# NGUON.net
KiCad netlist of a schematic drawn in Altium Designer
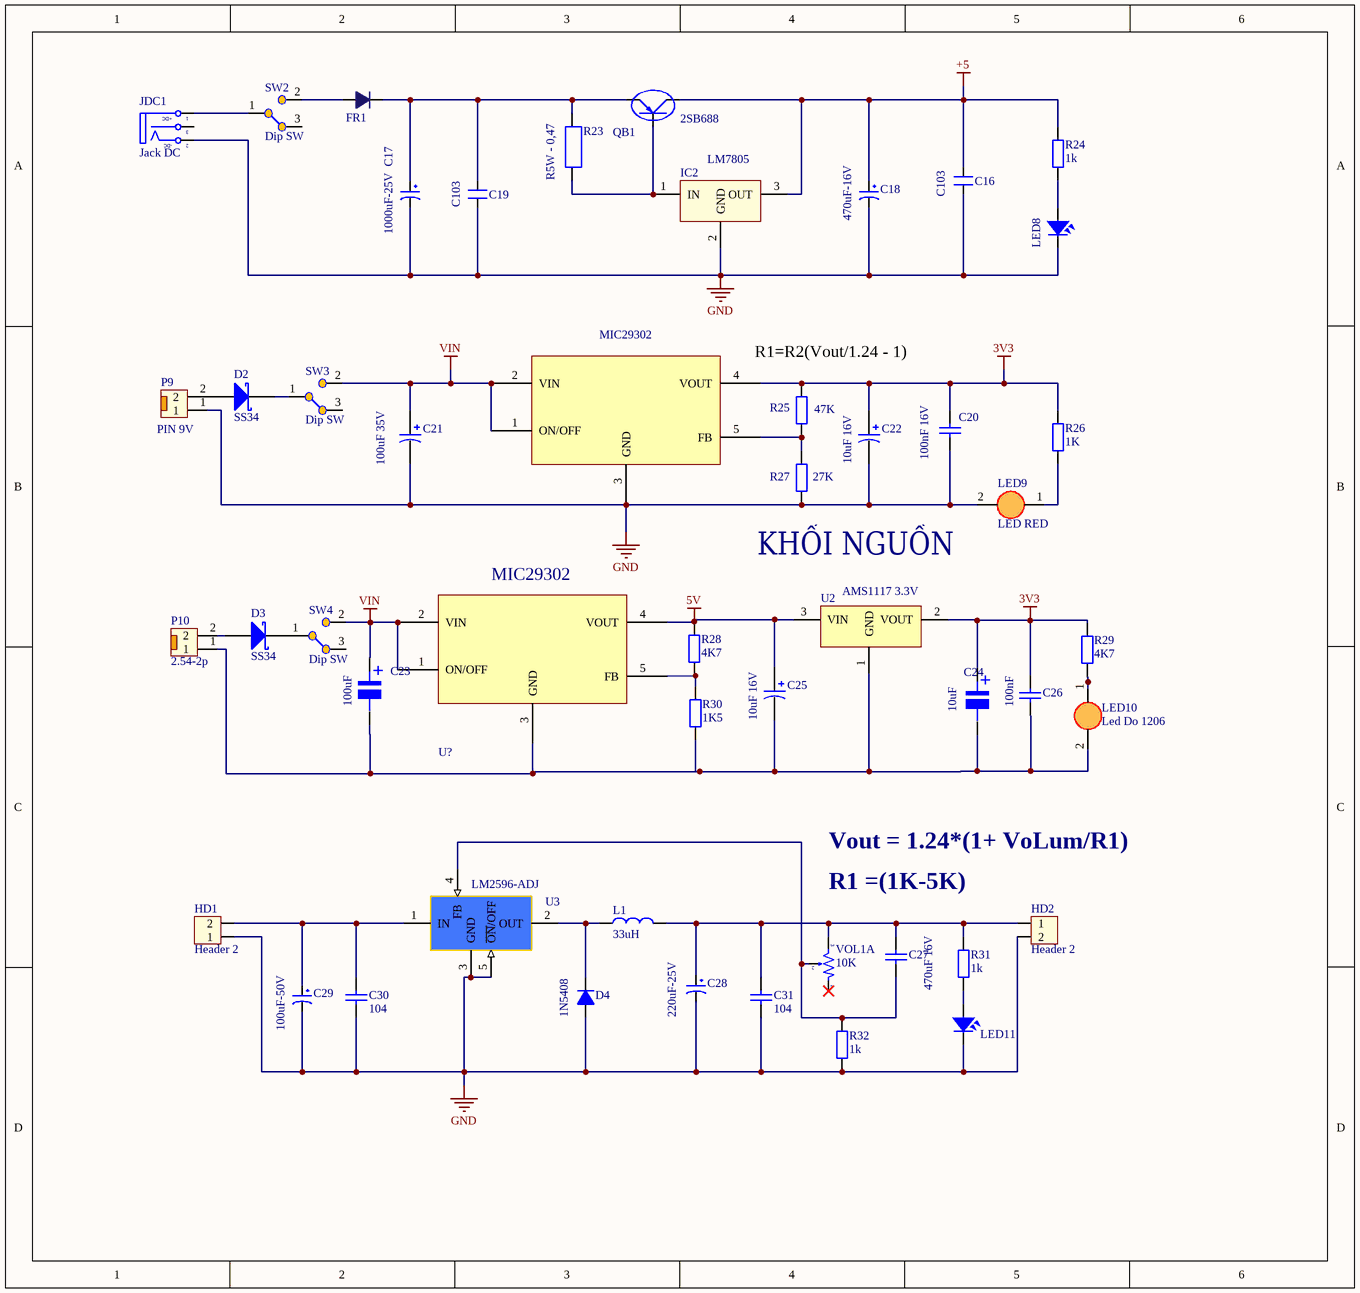
[diagram p0: NGUON.SchDoc]

(export (version "E")
  (design (tool "Eeschema 10.0.6"))
  (components
    (comp (ref "C16")
      (value "C103")
      (footprint "CN1")
      (description "Cap np  1pF - 472pF")
      (libsource (lib "syhaunguyen") (part "CN1"))
    )
    (comp (ref "C17")
      (value "1000uF-25V")
      (footprint "tu hoa 13mm")
      (description "Cắm")
      (libsource (lib "NhomLib") (part "Tu Hoa 1000uF 25V 13x21"))
    )
    (comp (ref "C18")
      (value "470uF-16V")
      (footprint "tu hoa 8mm")
      (description "Cắm")
      (libsource (lib "NhomLib") (part "Tu Hoa 470uF 16V 8x11"))
    )
    (comp (ref "C19")
      (value "C103")
      (footprint "CN1")
      (description "Cap np  1pF - 472pF")
      (libsource (lib "syhaunguyen") (part "CN1"))
    )
    (comp (ref "C20")
      (value "100nF 16V")
      (footprint "tu 0805")
      (description "Dán")
      (libsource (lib "SCH Chuan") (part "Tu 0805 22pF 50V 10%"))
    )
    (comp (ref "C21")
      (value "100uF 35V")
      (footprint "CAP_ALUM_SMD_100102_TYPE_G")
      (description "CAP ALUM 330uF 20% 35V SMD")
      (fields (field (name "MPN") "EEE-FK1C331P") (field (name "MFR") "Panasonic"))
      (libsource (lib "NhomLib") (part "EEE-FK1C331P"))
    )
    (comp (ref "C22")
      (value "10uF 16V")
      (footprint "CAP_ALUM_SMD_5054_TYPE_C")
      (description "CAP ALUM 33uF 20% 16V SMD")
      (fields (field (name "MPN") "EEE-FK1C330P") (field (name "MFR") "Panasonic"))
      (libsource (lib "NhomLib") (part "EEE-FK1C330P"))
    )
    (comp (ref "C23")
      (value "100uF")
      (footprint "tu nhom 10 (g)")
      (description "Dán")
      (libsource (lib "NhomLib") (part "Tu Nhom 100uF 35V"))
    )
    (comp (ref "C24")
      (value "10uF")
      (footprint "tu nhom 4 (b)")
      (description "Dán")
      (libsource (lib "NhomLib") (part "Tu Nhom 10uF 16V"))
    )
    (comp (ref "C25")
      (value "10uF 16V")
      (footprint "CAP_ALUM_SMD_5054_TYPE_C")
      (description "CAP ALUM 33uF 20% 16V SMD")
      (fields (field (name "MPN") "EEE-FK1C330P") (field (name "MFR") "Panasonic"))
      (libsource (lib "NhomLib") (part "EEE-FK1C330P"))
    )
    (comp (ref "C26")
      (value "100nF")
      (footprint "tu 0805")
      (description "Dán")
      (libsource (lib "NhomLib") (part "Tu 0805 220nF 50V 10%"))
    )
    (comp (ref "C27")
      (value "470uF 16V")
      (footprint "tu gom")
      (description "Cắm")
      (libsource (lib "NhomLib") (part "Tu gom 100 50V"))
    )
    (comp (ref "C28")
      (value "220uF-25V")
      (footprint "Tu hoa 8mm")
      (description "Cắm")
      (libsource (lib "NhomLib") (part "Tu Hoa 220uF 25V 8x10"))
    )
    (comp (ref "C29")
      (value "100uF-50V")
      (footprint "tu hoa 8mm")
      (description "Cắm")
      (libsource (lib "NhomLib") (part "Tu Hoa 100uF 50V 8x11"))
    )
    (comp (ref "C30")
      (value "104")
      (footprint "tu gom")
      (description "Cắm")
      (libsource (lib "NhomLib") (part "Tu gom 100 50V"))
    )
    (comp (ref "C31")
      (value "104")
      (footprint "tu gom")
      (description "Cắm")
      (libsource (lib "NhomLib") (part "Tu gom 100 50V"))
    )
    (comp (ref "D2")
      (value "SS34")
      (footprint "DIODE_DO214AC_SMA")
      (description "DIODE SCHOTTKY 40V 3A SMA")
      (libsource (lib "NhomLib") (part "SS34"))
    )
    (comp (ref "D3")
      (value "SS34")
      (footprint "DIODE_DO214AC_SMA")
      (description "DIODE SCHOTTKY 40V 3A SMA")
      (libsource (lib "NhomLib") (part "SS34"))
    )
    (comp (ref "D4")
      (value "1N5408")
      (footprint "D5A")
      (description "Diode 5A")
      (libsource (lib "syhaunguyen") (part "D5A"))
    )
    (comp (ref "FR1")
      (value "Diode FR307")
      (footprint "FR307")
      (description "Diode RECT FAST REC 1000V 3A DO-201AD")
      (fields (field (name "PUBLISHER") "Altium Limited"))
      (libsource (lib "VPMyLibrary") (part "Diode FR307"))
    )
    (comp (ref "HD1")
      (value "Header 2")
      (footprint "HED2")
      (description "Header 2 (Green)")
      (libsource (lib "") (part "Hed2_1"))
    )
    (comp (ref "HD2")
      (value "Header 2")
      (footprint "HED2")
      (description "Header 2 (Green)")
      (libsource (lib "NhomLib") (part "Hed2"))
    )
    (comp (ref "IC2")
      (value "LM7805")
      (footprint "QTO-220H3")
      (description "On ap +, from + 5 to + 24VDC")
      (libsource (lib "NhomLib") (part "LM78xx"))
    )
    (comp (ref "JDC1")
      (value "Jack DC")
      (footprint "DC-IN")
      (description "Cắm")
      (libsource (lib "NhomLib") (part "Jack DC"))
    )
    (comp (ref "L1")
      (value "33uH")
      (footprint "R1/4W")
      (description "Cắm")
      (libsource (lib "NhomLib") (part "Cuon cam 220uH"))
    )
    (comp (ref "LED8")
      (value "LED")
      (footprint "LED-5-RED")
      (description "LED Single colour Green and Red")
      (libsource (lib "syhaunguyen") (part "LED"))
    )
    (comp (ref "LED9")
      (value "LED RED")
      (footprint "led 0805")
      (description "Dán")
      (libsource (lib "SCH Chuan") (part "Led 0805 Do"))
    )
    (comp (ref "LED10")
      (value "Led Do 1206")
      (footprint "led 1206")
      (description "Dán")
      (libsource (lib "NhomLib") (part "Led 1206 Do"))
    )
    (comp (ref "LED11")
      (value "LED")
      (footprint "LED-5-RED")
      (description "LED Single colour Green and Red")
      (libsource (lib "syhaunguyen") (part "LED"))
    )
    (comp (ref "MIC2")
      (value "MIC29302")
      (footprint "Mic5V")
      (description "3A")
      (libsource (lib "node_mcu") (part "Mic5V"))
    )
    (comp (ref "MIC3")
      (value "U?")
      (footprint "Mic5V")
      (description "3A")
      (libsource (lib "node_mcu") (part "Mic5V"))
    )
    (comp (ref "P9")
      (value "PIN 9V")
      (footprint "Header Duc Thang 2P 2.54")
      (description "Cắm")
      (libsource (lib "NhomLib") (part "Header 2.54-2p Duc Thang"))
    )
    (comp (ref "P10")
      (value "2.54-2p")
      (footprint "Header Duc Thang 2P 2.54")
      (description "Cắm")
      (libsource (lib "NhomLib") (part "Header 2.54-2p Duc Thang"))
    )
    (comp (ref "QB1")
      (value "2SB688")
      (footprint "QTO-247")
      (description "Cắm")
      (libsource (lib "NhomLib") (part "B688"))
    )
    (comp (ref "R23")
      (value "R5W - 0,47")
      (footprint "R5W")
      (description "Resistor 5W")
      (libsource (lib "syhaunguyen") (part "R5W"))
    )
    (comp (ref "R24")
      (value "1k")
      (footprint "R1/4W")
      (description "Resistor 1/4W")
      (libsource (lib "syhaunguyen") (part "R1/4W"))
    )
    (comp (ref "R25")
      (value "47K")
      (footprint "tro 0805")
      (description "Dán")
      (libsource (lib "NhomLib") (part "Tro 0805 5% 10k"))
    )
    (comp (ref "R26")
      (value "1K")
      (footprint "tro 0805")
      (description "Dán")
      (libsource (lib "NhomLib") (part "Tro 0805 5% 10k"))
    )
    (comp (ref "R27")
      (value "27K")
      (footprint "tro 0805")
      (description "Dán")
      (libsource (lib "NhomLib") (part "Tro 0805 5% 10k"))
    )
    (comp (ref "R28")
      (value "4K7")
      (footprint "tro 0805")
      (description "Dán")
      (libsource (lib "SCH Chuan") (part "Tro 0805 5% 10k"))
    )
    (comp (ref "R29")
      (value "4K7")
      (footprint "tro 0805")
      (description "Dán")
      (libsource (lib "SCH Chuan") (part "Tro 0805 5% 10k"))
    )
    (comp (ref "R30")
      (value "1K5")
      (footprint "tro 0805")
      (description "Dán")
      (libsource (lib "SCH Chuan") (part "Tro 0805 5% 10k"))
    )
    (comp (ref "R31")
      (value "1k")
      (footprint "R1/4W")
      (description "Resistor 1/4W")
      (libsource (lib "syhaunguyen") (part "R1/4W"))
    )
    (comp (ref "R32")
      (value "1k")
      (footprint "R1/4W")
      (description "Resistor 1/4W")
      (libsource (lib "syhaunguyen") (part "R1/4W"))
    )
    (comp (ref "SW2")
      (value "Dip SW")
      (footprint "SW3P")
      (description "Dip Switch 3 pin")
      (libsource (lib "VPMyLibrary") (part "Switch3P"))
    )
    (comp (ref "SW3")
      (value "Dip SW")
      (footprint "SW3P")
      (description "Dip Switch 3 pin")
      (libsource (lib "VPMyLibrary") (part "Switch3P"))
    )
    (comp (ref "SW4")
      (value "Dip SW")
      (footprint "SW3P")
      (description "Dip Switch 3 pin")
      (libsource (lib "VPMyLibrary") (part "Switch3P"))
    )
    (comp (ref "U2")
      (value "AMS1117 3.3V")
      (footprint "SOT223")
      (description "Dán")
      (libsource (lib "NhomLib") (part "AMS1117 3.3V"))
    )
    (comp (ref "U3")
      (value "LM2596-ADJ")
      (footprint "D2-PACK5")
      (description "Simple Switcher 3A Step Down Voltage Regulator")
      (fields (field (name "PUBLISHER") "Altium Limited"))
      (libsource (lib "VPMyLibrary") (part "LM2596"))
    )
    (comp (ref "VOL1")
      (value "10K")
      (footprint "VR1")
      (description "Volume control Dual")
      (libsource (lib "SCH Chuan") (part "VOL-D"))
    )
  )
  (nets
    (net (code "1") (name "+5") (class "Default")
      (node (ref "C16") (pin "2") (pinfunction "2_2") (pintype "passive"))
      (node (ref "C18") (pin "1") (pinfunction "1_1") (pintype "passive"))
      (node (ref "IC2") (pin "3") (pinfunction "OUT_3") (pintype "passive"))
      (node (ref "QB1") (pin "2") (pinfunction "C_2") (pintype "passive"))
      (node (ref "R24") (pin "2") (pinfunction "2_2") (pintype "passive"))
    )
    (net (code "2") (name "3V3") (class "Default")
      (node (ref "C20") (pin "1") (pinfunction "1_1") (pintype "passive"))
      (node (ref "C22") (pin "1") (pinfunction "1_1") (pintype "passive"))
      (node (ref "C24") (pin "1") (pinfunction "1_1") (pintype "passive"))
      (node (ref "C26") (pin "1") (pinfunction "1_1") (pintype "passive"))
      (node (ref "MIC2") (pin "4") (pinfunction "VOUT_4") (pintype "passive"))
      (node (ref "R25") (pin "1") (pinfunction "1_1") (pintype "passive"))
      (node (ref "R26") (pin "2") (pinfunction "2_2") (pintype "passive"))
      (node (ref "R29") (pin "1") (pinfunction "1_1") (pintype "passive"))
      (node (ref "U2") (pin "2") (pinfunction "VOUT_2") (pintype "passive"))
    )
    (net (code "3") (name "5V") (class "Default")
      (node (ref "C25") (pin "1") (pinfunction "1_1") (pintype "passive"))
      (node (ref "MIC3") (pin "4") (pinfunction "VOUT_4") (pintype "passive"))
      (node (ref "R28") (pin "2") (pinfunction "2_2") (pintype "passive"))
      (node (ref "U2") (pin "3") (pinfunction "VIN_3") (pintype "passive"))
    )
    (net (code "4") (name "GND") (class "Default")
      (node (ref "C16") (pin "1") (pinfunction "1_1") (pintype "passive"))
      (node (ref "C17") (pin "2") (pinfunction "2_2") (pintype "passive"))
      (node (ref "C18") (pin "2") (pinfunction "2_2") (pintype "passive"))
      (node (ref "C19") (pin "1") (pinfunction "1_1") (pintype "passive"))
      (node (ref "C20") (pin "2") (pinfunction "2_2") (pintype "passive"))
      (node (ref "C21") (pin "2") (pinfunction "2_2") (pintype "passive"))
      (node (ref "C22") (pin "2") (pinfunction "2_2") (pintype "passive"))
      (node (ref "C28") (pin "2") (pinfunction "2_2") (pintype "passive"))
      (node (ref "C29") (pin "2") (pinfunction "2_2") (pintype "passive"))
      (node (ref "C30") (pin "2") (pinfunction "2_2") (pintype "passive"))
      (node (ref "C31") (pin "2") (pinfunction "2_2") (pintype "passive"))
      (node (ref "D4") (pin "1") (pinfunction "A_1") (pintype "passive"))
      (node (ref "HD1") (pin "1") (pinfunction "1_1") (pintype "passive"))
      (node (ref "HD2") (pin "2") (pinfunction "2_2") (pintype "passive"))
      (node (ref "IC2") (pin "2") (pinfunction "GND_2") (pintype "passive"))
      (node (ref "JDC1") (pin "2") (pinfunction "TN_2") (pintype "passive"))
      (node (ref "LED11") (pin "2") (pinfunction "2_2") (pintype "passive"))
      (node (ref "LED8") (pin "2") (pinfunction "2_2") (pintype "passive"))
      (node (ref "LED9") (pin "2") (pinfunction "K_2") (pintype "passive"))
      (node (ref "MIC2") (pin "3") (pinfunction "GND_3") (pintype "passive"))
      (node (ref "P9") (pin "1") (pinfunction "1_1") (pintype "passive"))
      (node (ref "R27") (pin "2") (pinfunction "2_2") (pintype "passive"))
      (node (ref "R32") (pin "1") (pinfunction "1_1") (pintype "passive"))
      (node (ref "U3") (pin "3") (pinfunction "GND_3") (pintype "power_in"))
      (node (ref "U3") (pin "5") (pinfunction "~{ON}/OFF_5") (pintype "input"))
    )
    (net (code "5") (name "Net-(C27-Pad1)") (class "Default")
      (node (ref "C27") (pin "1") (pinfunction "1_1") (pintype "passive"))
      (node (ref "C28") (pin "1") (pinfunction "1_1") (pintype "passive"))
      (node (ref "C31") (pin "1") (pinfunction "1_1") (pintype "passive"))
      (node (ref "HD2") (pin "1") (pinfunction "1_1") (pintype "passive"))
      (node (ref "L1") (pin "2") (pinfunction "2_2") (pintype "passive"))
      (node (ref "R31") (pin "2") (pinfunction "2_2") (pintype "passive"))
      (node (ref "VOL1") (pin "3") (pinfunction "3_3") (pintype "passive"))
    )
    (net (code "6") (name "Net-(D2-A)") (class "Default")
      (node (ref "D2") (pin "1") (pinfunction "A_1") (pintype "passive"))
      (node (ref "P9") (pin "2") (pinfunction "2_2") (pintype "passive"))
    )
    (net (code "7") (name "Net-(D2-K)") (class "Default")
      (node (ref "D2") (pin "2") (pinfunction "K_2") (pintype "passive"))
      (node (ref "SW3") (pin "1") (pinfunction "COM_1") (pintype "passive"))
    )
    (net (code "8") (name "Net-(D3-A)") (class "Default")
      (node (ref "D3") (pin "1") (pinfunction "A_1") (pintype "passive"))
      (node (ref "P10") (pin "2") (pinfunction "2_2") (pintype "passive"))
    )
    (net (code "9") (name "Net-(D3-K)") (class "Default")
      (node (ref "D3") (pin "2") (pinfunction "K_2") (pintype "passive"))
      (node (ref "SW4") (pin "1") (pinfunction "COM_1") (pintype "passive"))
    )
    (net (code "10") (name "Net-(D4-K)") (class "Default")
      (node (ref "D4") (pin "2") (pinfunction "K_2") (pintype "passive"))
      (node (ref "L1") (pin "1") (pinfunction "1_1") (pintype "passive"))
      (node (ref "U3") (pin "2") (pinfunction "OUT_2") (pintype "power_in"))
    )
    (net (code "11") (name "Net-(FR1-A)") (class "Default")
      (node (ref "FR1") (pin "1") (pinfunction "A_1") (pintype "passive"))
      (node (ref "SW2") (pin "2") (pinfunction "NC_2") (pintype "passive"))
    )
    (net (code "12") (name "Net-(FR1-K)") (class "Default")
      (node (ref "C17") (pin "1") (pinfunction "1_1") (pintype "passive"))
      (node (ref "C19") (pin "2") (pinfunction "2_2") (pintype "passive"))
      (node (ref "FR1") (pin "2") (pinfunction "K_2") (pintype "passive"))
      (node (ref "QB1") (pin "3") (pinfunction "E_3") (pintype "passive"))
      (node (ref "R23") (pin "2") (pinfunction "2_2") (pintype "passive"))
    )
    (net (code "13") (name "Net-(IC2-IN)") (class "Default")
      (node (ref "IC2") (pin "1") (pinfunction "IN_1") (pintype "passive"))
      (node (ref "QB1") (pin "1") (pinfunction "B_1") (pintype "passive"))
      (node (ref "R23") (pin "1") (pinfunction "1_1") (pintype "passive"))
    )
    (net (code "14") (name "Net-(JDC1-T)") (class "Default")
      (node (ref "JDC1") (pin "1") (pinfunction "T_1") (pintype "passive"))
      (node (ref "SW2") (pin "1") (pinfunction "COM_1") (pintype "passive"))
    )
    (net (code "15") (name "Net-(LED8-Pad1)") (class "Default")
      (node (ref "LED8") (pin "1") (pinfunction "1_1") (pintype "passive"))
      (node (ref "R24") (pin "1") (pinfunction "1_1") (pintype "passive"))
    )
    (net (code "16") (name "Net-(LED9-A)") (class "Default")
      (node (ref "LED9") (pin "1") (pinfunction "A_1") (pintype "passive"))
      (node (ref "R26") (pin "1") (pinfunction "1_1") (pintype "passive"))
    )
    (net (code "17") (name "Net-(LED10-A)") (class "Default")
      (node (ref "LED10") (pin "1") (pinfunction "A_1") (pintype "passive"))
      (node (ref "R29") (pin "2") (pinfunction "2_2") (pintype "passive"))
    )
    (net (code "18") (name "Net-(LED10-K)") (class "Default")
      (node (ref "C23") (pin "2") (pinfunction "2_2") (pintype "passive"))
      (node (ref "C24") (pin "2") (pinfunction "2_2") (pintype "passive"))
      (node (ref "C25") (pin "2") (pinfunction "2_2") (pintype "passive"))
      (node (ref "C26") (pin "2") (pinfunction "2_2") (pintype "passive"))
      (node (ref "LED10") (pin "2") (pinfunction "K_2") (pintype "passive"))
      (node (ref "MIC3") (pin "3") (pinfunction "GND_3") (pintype "passive"))
      (node (ref "P10") (pin "1") (pinfunction "1_1") (pintype "passive"))
      (node (ref "R30") (pin "1") (pinfunction "1_1") (pintype "passive"))
      (node (ref "U2") (pin "1") (pinfunction "GND_1") (pintype "passive"))
    )
    (net (code "19") (name "Net-(LED11-Pad1)") (class "Default")
      (node (ref "LED11") (pin "1") (pinfunction "1_1") (pintype "passive"))
      (node (ref "R31") (pin "1") (pinfunction "1_1") (pintype "passive"))
    )
    (net (code "20") (name "Net-(MIC2-FB)") (class "Default")
      (node (ref "MIC2") (pin "5") (pinfunction "FB_5") (pintype "passive"))
      (node (ref "R25") (pin "2") (pinfunction "2_2") (pintype "passive"))
      (node (ref "R27") (pin "1") (pinfunction "1_1") (pintype "passive"))
    )
    (net (code "21") (name "Net-(MIC3-FB)") (class "Default")
      (node (ref "MIC3") (pin "5") (pinfunction "FB_5") (pintype "passive"))
      (node (ref "R28") (pin "1") (pinfunction "1_1") (pintype "passive"))
      (node (ref "R30") (pin "2") (pinfunction "2_2") (pintype "passive"))
    )
    (net (code "22") (name "Net-(U3-FB)") (class "Default")
      (node (ref "C27") (pin "2") (pinfunction "2_2") (pintype "passive"))
      (node (ref "R32") (pin "2") (pinfunction "2_2") (pintype "passive"))
      (node (ref "U3") (pin "4") (pinfunction "FB_4") (pintype "input"))
      (node (ref "VOL1") (pin "2") (pinfunction "2_2") (pintype "passive"))
    )
    (net (code "23") (name "Net-(U3-IN)") (class "Default")
      (node (ref "C29") (pin "1") (pinfunction "1_1") (pintype "passive"))
      (node (ref "C30") (pin "1") (pinfunction "1_1") (pintype "passive"))
      (node (ref "HD1") (pin "2") (pinfunction "2_2") (pintype "passive"))
      (node (ref "U3") (pin "1") (pinfunction "IN_1") (pintype "power_in"))
    )
    (net (code "24") (name "VIN") (class "Default")
      (node (ref "C21") (pin "1") (pinfunction "1_1") (pintype "passive"))
      (node (ref "C23") (pin "1") (pinfunction "1_1") (pintype "passive"))
      (node (ref "MIC2") (pin "1") (pinfunction "ON/OFF_1") (pintype "passive"))
      (node (ref "MIC2") (pin "2") (pinfunction "VIN_2") (pintype "passive"))
      (node (ref "MIC3") (pin "1") (pinfunction "ON/OFF_1") (pintype "passive"))
      (node (ref "MIC3") (pin "2") (pinfunction "VIN_2") (pintype "passive"))
      (node (ref "SW3") (pin "2") (pinfunction "NC_2") (pintype "passive"))
      (node (ref "SW4") (pin "2") (pinfunction "NC_2") (pintype "passive"))
    )
    (net (code "25") (name "unconnected-(JDC1-S-Pad3)") (class "Default")
      (node (ref "JDC1") (pin "3") (pinfunction "S_3") (pintype "power_in"))
    )
    (net (code "26") (name "unconnected-(SW2-NO-Pad3)") (class "Default")
      (node (ref "SW2") (pin "3") (pinfunction "NO_3") (pintype "passive"))
    )
    (net (code "27") (name "unconnected-(SW3-NO-Pad3)") (class "Default")
      (node (ref "SW3") (pin "3") (pinfunction "NO_3") (pintype "passive"))
    )
    (net (code "28") (name "unconnected-(SW4-NO-Pad3)") (class "Default")
      (node (ref "SW4") (pin "3") (pinfunction "NO_3") (pintype "passive"))
    )
    (net (code "29") (name "unconnected-(VOL1-Pad1)") (class "Default")
      (node (ref "VOL1") (pin "1") (pinfunction "1_1") (pintype "passive+no_connect"))
    )
  )
)
